# sonoff_opto.net
KiCad netlist of a schematic drawn in EAGLE
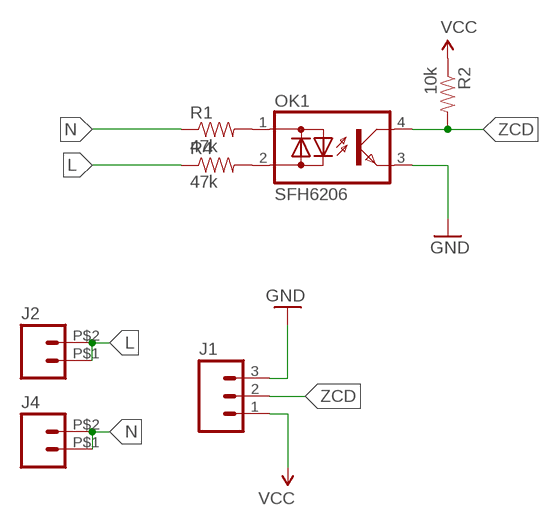
[diagram p0: schematic, sheet 1]

(export (version "E")
  (design (tool "Eeschema 10.0.6"))
  (components
    (comp (ref "J1")
      (value "M03PTH")
      (footprint "eagle-import:1X03")
      (libsource (lib "eagle-import") (part "M03PTH"))
    )
    (comp (ref "J2")
      (value "M02PTH2")
      (footprint "eagle-import:1X02_BIG")
      (libsource (lib "eagle-import") (part "M02PTH2"))
    )
    (comp (ref "J4")
      (value "M02PTH2")
      (footprint "eagle-import:1X02_BIG")
      (libsource (lib "eagle-import") (part "M02PTH2"))
    )
    (comp (ref "OK1")
      (value "SFH6206")
      (footprint "eagle-import:DIL4-SMD")
      (libsource (lib "eagle-import") (part "SFH6206"))
    )
    (comp (ref "R1")
      (value "47k")
      (footprint "eagle-import:AXIAL-0.4")
      (libsource (lib "eagle-import") (part "RESISTORPTH-1/4W"))
    )
    (comp (ref "R2")
      (value "10k")
      (footprint "eagle-import:0805")
      (libsource (lib "eagle-import") (part "RESISTOR0805-RES"))
    )
    (comp (ref "R4")
      (value "47k")
      (footprint "eagle-import:AXIAL-0.4")
      (libsource (lib "eagle-import") (part "RESISTORPTH-1/4W"))
    )
  )
  (nets
    (net (code "1") (name "GND") (class "Default")
      (node (ref "J1") (pin "3") (pinfunction "3_3") (pintype "passive"))
      (node (ref "OK1") (pin "3") (pinfunction "E_3") (pintype "passive"))
    )
    (net (code "2") (name "L") (class "Default")
      (node (ref "J2") (pin "P$1") (pinfunction "1_P$1") (pintype "passive"))
      (node (ref "J2") (pin "P$2") (pinfunction "2_P$2") (pintype "passive"))
      (node (ref "R4") (pin "P$1") (pinfunction "1_P$1") (pintype "passive"))
    )
    (net (code "3") (name "N") (class "Default")
      (node (ref "J4") (pin "P$1") (pinfunction "1_P$1") (pintype "passive"))
      (node (ref "J4") (pin "P$2") (pinfunction "2_P$2") (pintype "passive"))
      (node (ref "R1") (pin "P$1") (pinfunction "1_P$1") (pintype "passive"))
    )
    (net (code "4") (name "Net-(OK1-AC1)") (class "Default")
      (node (ref "OK1") (pin "1") (pinfunction "AC1_1") (pintype "passive"))
      (node (ref "R1") (pin "P$2") (pinfunction "2_P$2") (pintype "passive"))
    )
    (net (code "5") (name "Net-(OK1-AC2)") (class "Default")
      (node (ref "OK1") (pin "2") (pinfunction "AC2_2") (pintype "passive"))
      (node (ref "R4") (pin "P$2") (pinfunction "2_P$2") (pintype "passive"))
    )
    (net (code "6") (name "VCC") (class "Default")
      (node (ref "J1") (pin "1") (pinfunction "1_1") (pintype "passive"))
      (node (ref "R2") (pin "1") (pinfunction "1_1") (pintype "passive"))
    )
    (net (code "7") (name "ZCD") (class "Default")
      (node (ref "J1") (pin "2") (pinfunction "2_2") (pintype "passive"))
      (node (ref "OK1") (pin "4") (pinfunction "C_4") (pintype "passive"))
      (node (ref "R2") (pin "2") (pinfunction "2_2") (pintype "passive"))
    )
  )
)
